# 80PIN_FMU3_REV_C.net
KiCad netlist of a schematic drawn in Altium Designer
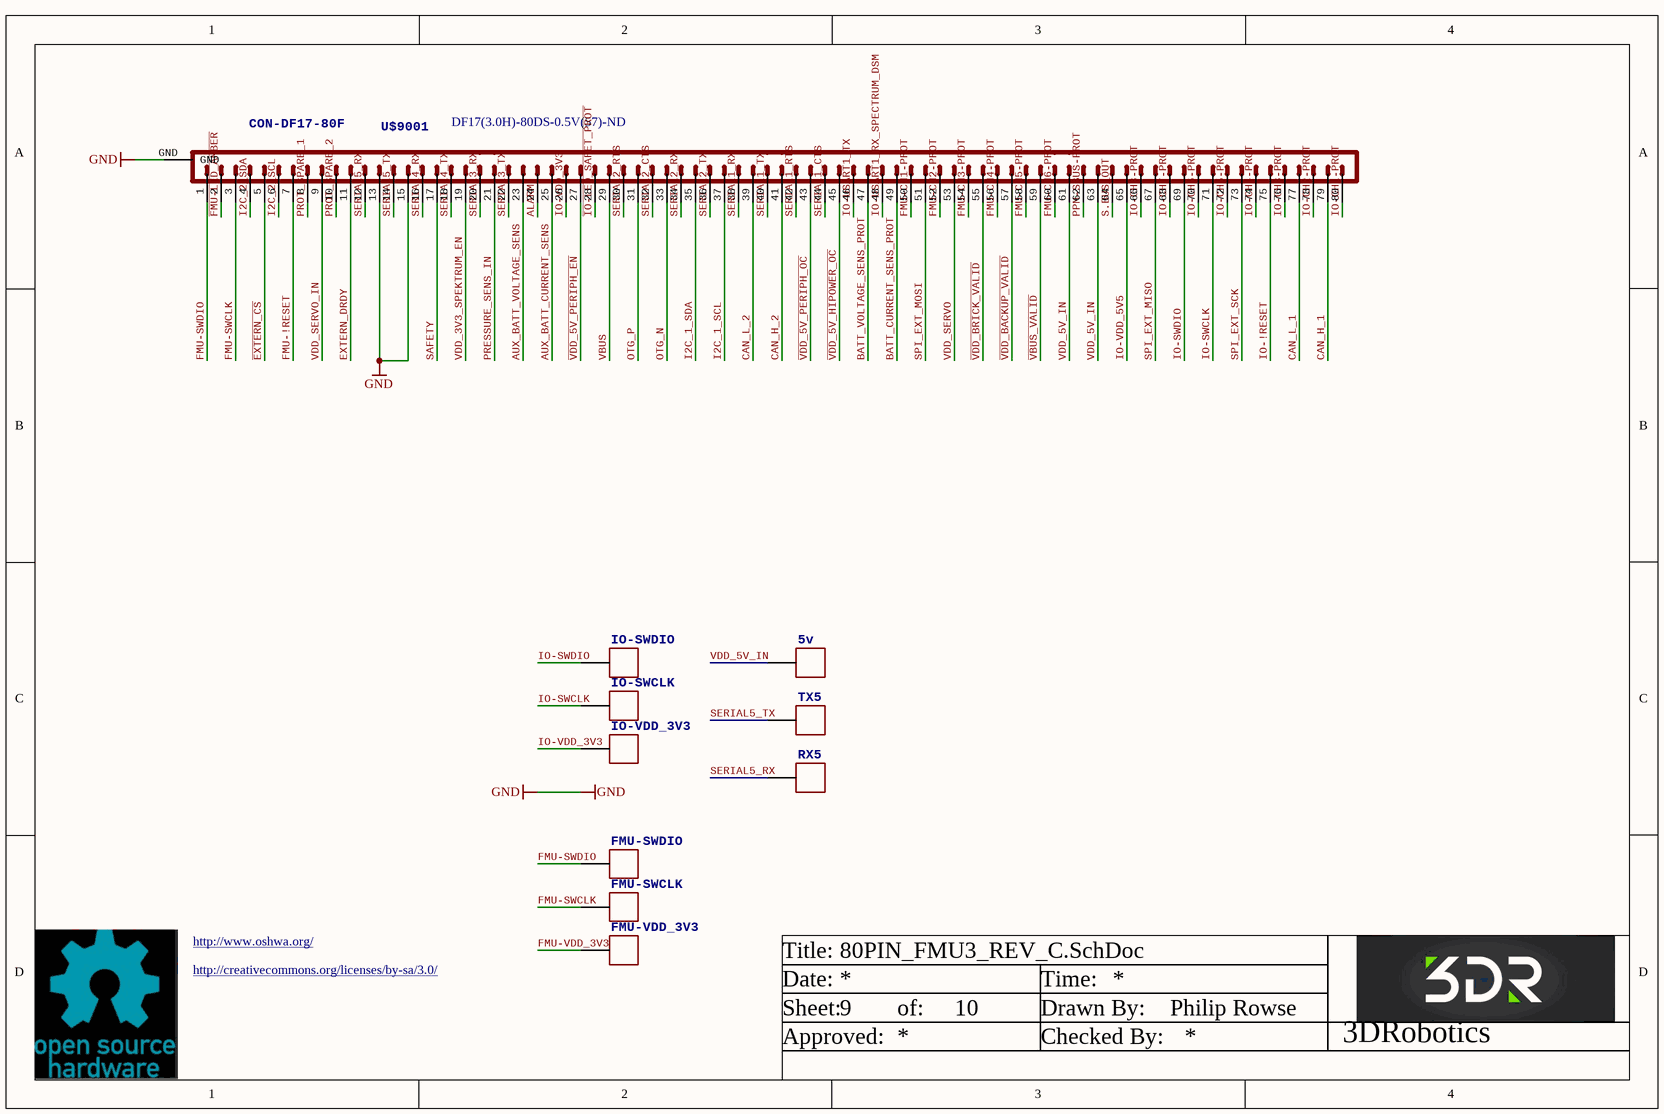
[diagram p0: 80PIN_FMU3_REV_C.SchDoc]

(export (version "E")
  (design (tool "Eeschema 10.0.6"))
  (components
    (comp (ref "5v") (value "PAD.04") (footprint "PAD.04X.04") (libsource (lib "pixhawk2") (part "PAD.04")))
    (comp (ref "FMU-SWCLK")
      (value "PAD.04")
      (footprint "PAD.04X.04")
      (libsource (lib "pixhawk2") (part "PAD.04"))
    )
    (comp (ref "FMU-SWDIO")
      (value "PAD.04")
      (footprint "PAD.04X.04")
      (libsource (lib "pixhawk2") (part "PAD.04"))
    )
    (comp (ref "FMU-VDD_3V3")
      (value "PAD.04")
      (footprint "PAD.04X.04")
      (libsource (lib "pixhawk2") (part "PAD.04"))
    )
    (comp (ref "IO-SWCLK")
      (value "PAD.04")
      (footprint "PAD.04X.04")
      (libsource (lib "pixhawk2") (part "PAD.04"))
    )
    (comp (ref "IO-SWDIO")
      (value "PAD.04")
      (footprint "PAD.04X.04")
      (libsource (lib "pixhawk2") (part "PAD.04"))
    )
    (comp (ref "IO-VDD_3V3")
      (value "PAD.04")
      (footprint "PAD.04X.04")
      (libsource (lib "pixhawk2") (part "PAD.04"))
    )
    (comp (ref "RX5") (value "PAD.04") (footprint "PAD.04X.04") (libsource (lib "pixhawk2") (part "PAD.04")))
    (comp (ref "TX5") (value "PAD.04") (footprint "PAD.04X.04") (libsource (lib "pixhawk2") (part "PAD.04")))
    (comp (ref "U$9001")
      (value "CON-DF17-80F")
      (footprint "CON-DF17-80F")
      (description "CONN RECEPT 80POS .5MM SMD W/FIT")
      (fields
        (field (name "SUPPLIER PART NUMBER 1") "DF17(3.0H)-80DS-0.5V(57)-ND")
        (field (name "3DR_PARTNO") "ECM0518")
        (field (name "PARTNO") "DF17(3.0H)-80DS-0.5V(57)")
      )
      (libsource (lib "pixhawk2") (part "CON-DF17-80F"))
    )
  )
  (nets
    (net (code "1") (name "/ALARM") (class "Default")
      (node (ref "U$9001") (pin "24") (pinfunction "24_24") (pintype "passive"))
    )
    (net (code "2") (name "/AUX_BATT_CURRENT_SENS") (class "Default")
      (node (ref "U$9001") (pin "25") (pinfunction "25_25") (pintype "passive"))
    )
    (net (code "3") (name "/AUX_BATT_VOLTAGE_SENS") (class "Default")
      (node (ref "U$9001") (pin "23") (pinfunction "23_23") (pintype "passive"))
    )
    (net (code "4") (name "/BATT_CURRENT_SENS_PROT") (class "Default")
      (node (ref "U$9001") (pin "49") (pinfunction "49_49") (pintype "passive"))
    )
    (net (code "5") (name "/BATT_VOLTAGE_SENS_PROT") (class "Default")
      (node (ref "U$9001") (pin "47") (pinfunction "47_47") (pintype "passive"))
    )
    (net (code "6") (name "/CAN_H_1") (class "Default")
      (node (ref "U$9001") (pin "79") (pinfunction "79_79") (pintype "passive"))
    )
    (net (code "7") (name "/CAN_H_2") (class "Default")
      (node (ref "U$9001") (pin "41") (pinfunction "41_41") (pintype "passive"))
    )
    (net (code "8") (name "/CAN_L_1") (class "Default")
      (node (ref "U$9001") (pin "77") (pinfunction "77_77") (pintype "passive"))
    )
    (net (code "9") (name "/CAN_L_2") (class "Default")
      (node (ref "U$9001") (pin "39") (pinfunction "39_39") (pintype "passive"))
    )
    (net (code "10") (name "/EXTERN_DRDY") (class "Default")
      (node (ref "U$9001") (pin "11") (pinfunction "11_11") (pintype "passive"))
    )
    (net (code "11") (name "/FMU-!RESET") (class "Default")
      (node (ref "U$9001") (pin "7") (pinfunction "7_7") (pintype "passive"))
    )
    (net (code "12") (name "/FMU-CH1-PROT") (class "Default")
      (node (ref "U$9001") (pin "50") (pinfunction "50_50") (pintype "passive"))
    )
    (net (code "13") (name "/FMU-CH2-PROT") (class "Default")
      (node (ref "U$9001") (pin "52") (pinfunction "52_52") (pintype "passive"))
    )
    (net (code "14") (name "/FMU-CH3-PROT") (class "Default")
      (node (ref "U$9001") (pin "54") (pinfunction "54_54") (pintype "passive"))
    )
    (net (code "15") (name "/FMU-CH4-PROT") (class "Default")
      (node (ref "U$9001") (pin "56") (pinfunction "56_56") (pintype "passive"))
    )
    (net (code "16") (name "/FMU-CH5-PROT") (class "Default")
      (node (ref "U$9001") (pin "58") (pinfunction "58_58") (pintype "passive"))
    )
    (net (code "17") (name "/FMU-CH6-PROT") (class "Default")
      (node (ref "U$9001") (pin "60") (pinfunction "60_60") (pintype "passive"))
    )
    (net (code "18") (name "/FMU-SWCLK") (class "Default")
      (node (ref "FMU-SWCLK") (pin "P$1") (pinfunction "P$1_P$1") (pintype "passive"))
      (node (ref "U$9001") (pin "3") (pinfunction "3_3") (pintype "passive"))
    )
    (net (code "19") (name "/FMU-SWDIO") (class "Default")
      (node (ref "FMU-SWDIO") (pin "P$1") (pinfunction "P$1_P$1") (pintype "passive"))
      (node (ref "U$9001") (pin "1") (pinfunction "1_1") (pintype "passive"))
    )
    (net (code "20") (name "/FMU-VDD_3V3") (class "Default")
      (node (ref "FMU-VDD_3V3") (pin "P$1") (pinfunction "P$1_P$1") (pintype "passive"))
    )
    (net (code "21") (name "/I2C_1_SCL") (class "Default")
      (node (ref "U$9001") (pin "37") (pinfunction "37_37") (pintype "passive"))
    )
    (net (code "22") (name "/I2C_1_SDA") (class "Default")
      (node (ref "U$9001") (pin "35") (pinfunction "35_35") (pintype "passive"))
    )
    (net (code "23") (name "/I2C_2_SCL") (class "Default")
      (node (ref "U$9001") (pin "6") (pinfunction "6_6") (pintype "passive"))
    )
    (net (code "24") (name "/I2C_2_SDA") (class "Default")
      (node (ref "U$9001") (pin "4") (pinfunction "4_4") (pintype "passive"))
    )
    (net (code "25") (name "/IO-!RESET") (class "Default")
      (node (ref "U$9001") (pin "75") (pinfunction "75_75") (pintype "passive"))
    )
    (net (code "26") (name "/IO-CH1-PROT") (class "Default")
      (node (ref "U$9001") (pin "80") (pinfunction "80_80") (pintype "passive"))
    )
    (net (code "27") (name "/IO-CH2-PROT") (class "Default")
      (node (ref "U$9001") (pin "78") (pinfunction "78_78") (pintype "passive"))
    )
    (net (code "28") (name "/IO-CH3-PROT") (class "Default")
      (node (ref "U$9001") (pin "76") (pinfunction "76_76") (pintype "passive"))
    )
    (net (code "29") (name "/IO-CH4-PROT") (class "Default")
      (node (ref "U$9001") (pin "74") (pinfunction "74_74") (pintype "passive"))
    )
    (net (code "30") (name "/IO-CH5-PROT") (class "Default")
      (node (ref "U$9001") (pin "72") (pinfunction "72_72") (pintype "passive"))
    )
    (net (code "31") (name "/IO-CH6-PROT") (class "Default")
      (node (ref "U$9001") (pin "70") (pinfunction "70_70") (pintype "passive"))
    )
    (net (code "32") (name "/IO-CH7-PROT") (class "Default")
      (node (ref "U$9001") (pin "68") (pinfunction "68_68") (pintype "passive"))
    )
    (net (code "33") (name "/IO-CH8-PROT") (class "Default")
      (node (ref "U$9001") (pin "66") (pinfunction "66_66") (pintype "passive"))
    )
    (net (code "34") (name "/IO-SWCLK") (class "Default")
      (node (ref "IO-SWCLK") (pin "P$1") (pinfunction "P$1_P$1") (pintype "passive"))
      (node (ref "U$9001") (pin "71") (pinfunction "71_71") (pintype "passive"))
    )
    (net (code "35") (name "/IO-SWDIO") (class "Default")
      (node (ref "IO-SWDIO") (pin "P$1") (pinfunction "P$1_P$1") (pintype "passive"))
      (node (ref "U$9001") (pin "69") (pinfunction "69_69") (pintype "passive"))
    )
    (net (code "36") (name "/IO-USART1_RX_SPECTRUM_DSM") (class "Default")
      (node (ref "U$9001") (pin "48") (pinfunction "48_48") (pintype "passive"))
    )
    (net (code "37") (name "/IO-USART1_TX") (class "Default")
      (node (ref "U$9001") (pin "46") (pinfunction "46_46") (pintype "passive"))
    )
    (net (code "38") (name "/IO-VDD_3V3") (class "Default")
      (node (ref "IO-VDD_3V3") (pin "P$1") (pinfunction "P$1_P$1") (pintype "passive"))
      (node (ref "U$9001") (pin "26") (pinfunction "26_26") (pintype "passive"))
    )
    (net (code "39") (name "/IO-VDD_5V5") (class "Default")
      (node (ref "U$9001") (pin "65") (pinfunction "65_65") (pintype "passive"))
    )
    (net (code "40") (name "/OTG_N") (class "Default")
      (node (ref "U$9001") (pin "33") (pinfunction "33_33") (pintype "passive"))
    )
    (net (code "41") (name "/OTG_P") (class "Default")
      (node (ref "U$9001") (pin "31") (pinfunction "31_31") (pintype "passive"))
    )
    (net (code "42") (name "/PPM-SBUS-PROT") (class "Default")
      (node (ref "U$9001") (pin "62") (pinfunction "62_62") (pintype "passive"))
    )
    (net (code "43") (name "/PRESSURE_SENS_IN") (class "Default")
      (node (ref "U$9001") (pin "21") (pinfunction "21_21") (pintype "passive"))
    )
    (net (code "44") (name "/PROT_SPARE_1") (class "Default")
      (node (ref "U$9001") (pin "8") (pinfunction "8_8") (pintype "passive"))
    )
    (net (code "45") (name "/PROT_SPARE_2") (class "Default")
      (node (ref "U$9001") (pin "10") (pinfunction "10_10") (pintype "passive"))
    )
    (net (code "46") (name "/S.BUS_OUT") (class "Default")
      (node (ref "U$9001") (pin "64") (pinfunction "64_64") (pintype "passive"))
    )
    (net (code "47") (name "/SAFETY") (class "Default")
      (node (ref "U$9001") (pin "17") (pinfunction "17_17") (pintype "passive"))
    )
    (net (code "48") (name "/SERIAL1_CTS") (class "Default")
      (node (ref "U$9001") (pin "44") (pinfunction "44_44") (pintype "passive"))
    )
    (net (code "49") (name "/SERIAL1_RTS") (class "Default")
      (node (ref "U$9001") (pin "42") (pinfunction "42_42") (pintype "passive"))
    )
    (net (code "50") (name "/SERIAL1_RX") (class "Default")
      (node (ref "U$9001") (pin "38") (pinfunction "38_38") (pintype "passive"))
    )
    (net (code "51") (name "/SERIAL1_TX") (class "Default")
      (node (ref "U$9001") (pin "40") (pinfunction "40_40") (pintype "passive"))
    )
    (net (code "52") (name "/SERIAL2_CTS") (class "Default")
      (node (ref "U$9001") (pin "32") (pinfunction "32_32") (pintype "passive"))
    )
    (net (code "53") (name "/SERIAL2_RTS") (class "Default")
      (node (ref "U$9001") (pin "30") (pinfunction "30_30") (pintype "passive"))
    )
    (net (code "54") (name "/SERIAL2_RX") (class "Default")
      (node (ref "U$9001") (pin "34") (pinfunction "34_34") (pintype "passive"))
    )
    (net (code "55") (name "/SERIAL2_TX") (class "Default")
      (node (ref "U$9001") (pin "36") (pinfunction "36_36") (pintype "passive"))
    )
    (net (code "56") (name "/SERIAL3_RX") (class "Default")
      (node (ref "U$9001") (pin "20") (pinfunction "20_20") (pintype "passive"))
    )
    (net (code "57") (name "/SERIAL3_TX") (class "Default")
      (node (ref "U$9001") (pin "22") (pinfunction "22_22") (pintype "passive"))
    )
    (net (code "58") (name "/SERIAL4_RX") (class "Default")
      (node (ref "U$9001") (pin "16") (pinfunction "16_16") (pintype "passive"))
    )
    (net (code "59") (name "/SERIAL4_TX") (class "Default")
      (node (ref "U$9001") (pin "18") (pinfunction "18_18") (pintype "passive"))
    )
    (net (code "60") (name "/SERIAL5_RX") (class "Default")
      (node (ref "RX5") (pin "P$1") (pinfunction "P$1_P$1") (pintype "passive"))
      (node (ref "U$9001") (pin "12") (pinfunction "12_12") (pintype "passive"))
    )
    (net (code "61") (name "/SERIAL5_TX") (class "Default")
      (node (ref "TX5") (pin "P$1") (pinfunction "P$1_P$1") (pintype "passive"))
      (node (ref "U$9001") (pin "14") (pinfunction "14_14") (pintype "passive"))
    )
    (net (code "62") (name "/SPI_EXT_MISO") (class "Default")
      (node (ref "U$9001") (pin "67") (pinfunction "67_67") (pintype "passive"))
    )
    (net (code "63") (name "/SPI_EXT_MOSI") (class "Default")
      (node (ref "U$9001") (pin "51") (pinfunction "51_51") (pintype "passive"))
    )
    (net (code "64") (name "/SPI_EXT_SCK") (class "Default")
      (node (ref "U$9001") (pin "73") (pinfunction "73_73") (pintype "passive"))
    )
    (net (code "65") (name "/VBUS") (class "Default")
      (node (ref "U$9001") (pin "29") (pinfunction "29_29") (pintype "passive"))
    )
    (net (code "66") (name "/VDD_3V3_SPEKTRUM_EN") (class "Default")
      (node (ref "U$9001") (pin "19") (pinfunction "19_19") (pintype "passive"))
    )
    (net (code "67") (name "/VDD_5V_IN") (class "Default")
      (node (ref "5v") (pin "P$1") (pinfunction "P$1_P$1") (pintype "passive"))
      (node (ref "U$9001") (pin "61") (pinfunction "61_61") (pintype "passive"))
      (node (ref "U$9001") (pin "63") (pinfunction "63_63") (pintype "passive"))
    )
    (net (code "68") (name "/VDD_SERVO") (class "Default")
      (node (ref "U$9001") (pin "53") (pinfunction "53_53") (pintype "passive"))
    )
    (net (code "69") (name "/VDD_SERVO_IN") (class "Default")
      (node (ref "U$9001") (pin "9") (pinfunction "9_9") (pintype "passive"))
    )
    (net (code "70") (name "/~{EXTERN_CS}") (class "Default")
      (node (ref "U$9001") (pin "5") (pinfunction "5_5") (pintype "passive"))
    )
    (net (code "71") (name "/~{FMU-LED_AMBER}") (class "Default")
      (node (ref "U$9001") (pin "2") (pinfunction "2_2") (pintype "passive"))
    )
    (net (code "72") (name "/~{IO-LED_SAFET_PROT}") (class "Default")
      (node (ref "U$9001") (pin "28") (pinfunction "28_28") (pintype "passive"))
    )
    (net (code "73") (name "/~{VBUS_VALID}") (class "Default")
      (node (ref "U$9001") (pin "59") (pinfunction "59_59") (pintype "passive"))
    )
    (net (code "74") (name "/~{VDD_5V_HIPOWER_OC}") (class "Default")
      (node (ref "U$9001") (pin "45") (pinfunction "45_45") (pintype "passive"))
    )
    (net (code "75") (name "/~{VDD_5V_PERIPH_EN}") (class "Default")
      (node (ref "U$9001") (pin "27") (pinfunction "27_27") (pintype "passive"))
    )
    (net (code "76") (name "/~{VDD_5V_PERIPH_OC}") (class "Default")
      (node (ref "U$9001") (pin "43") (pinfunction "43_43") (pintype "passive"))
    )
    (net (code "77") (name "/~{VDD_BACKUP_VALID}") (class "Default")
      (node (ref "U$9001") (pin "57") (pinfunction "57_57") (pintype "passive"))
    )
    (net (code "78") (name "/~{VDD_BRICK_VALID}") (class "Default")
      (node (ref "U$9001") (pin "55") (pinfunction "55_55") (pintype "passive"))
    )
    (net (code "79") (name "GND") (class "Default")
      (node (ref "U$9001") (pin "13") (pinfunction "13_13") (pintype "passive"))
      (node (ref "U$9001") (pin "15") (pinfunction "15_15") (pintype "passive"))
      (node (ref "U$9001") (pin "GND") (pinfunction "GND_GND") (pintype "passive"))
    )
  )
)
